# Safety_Logic.net
KiCad netlist of a schematic drawn in Altium Designer
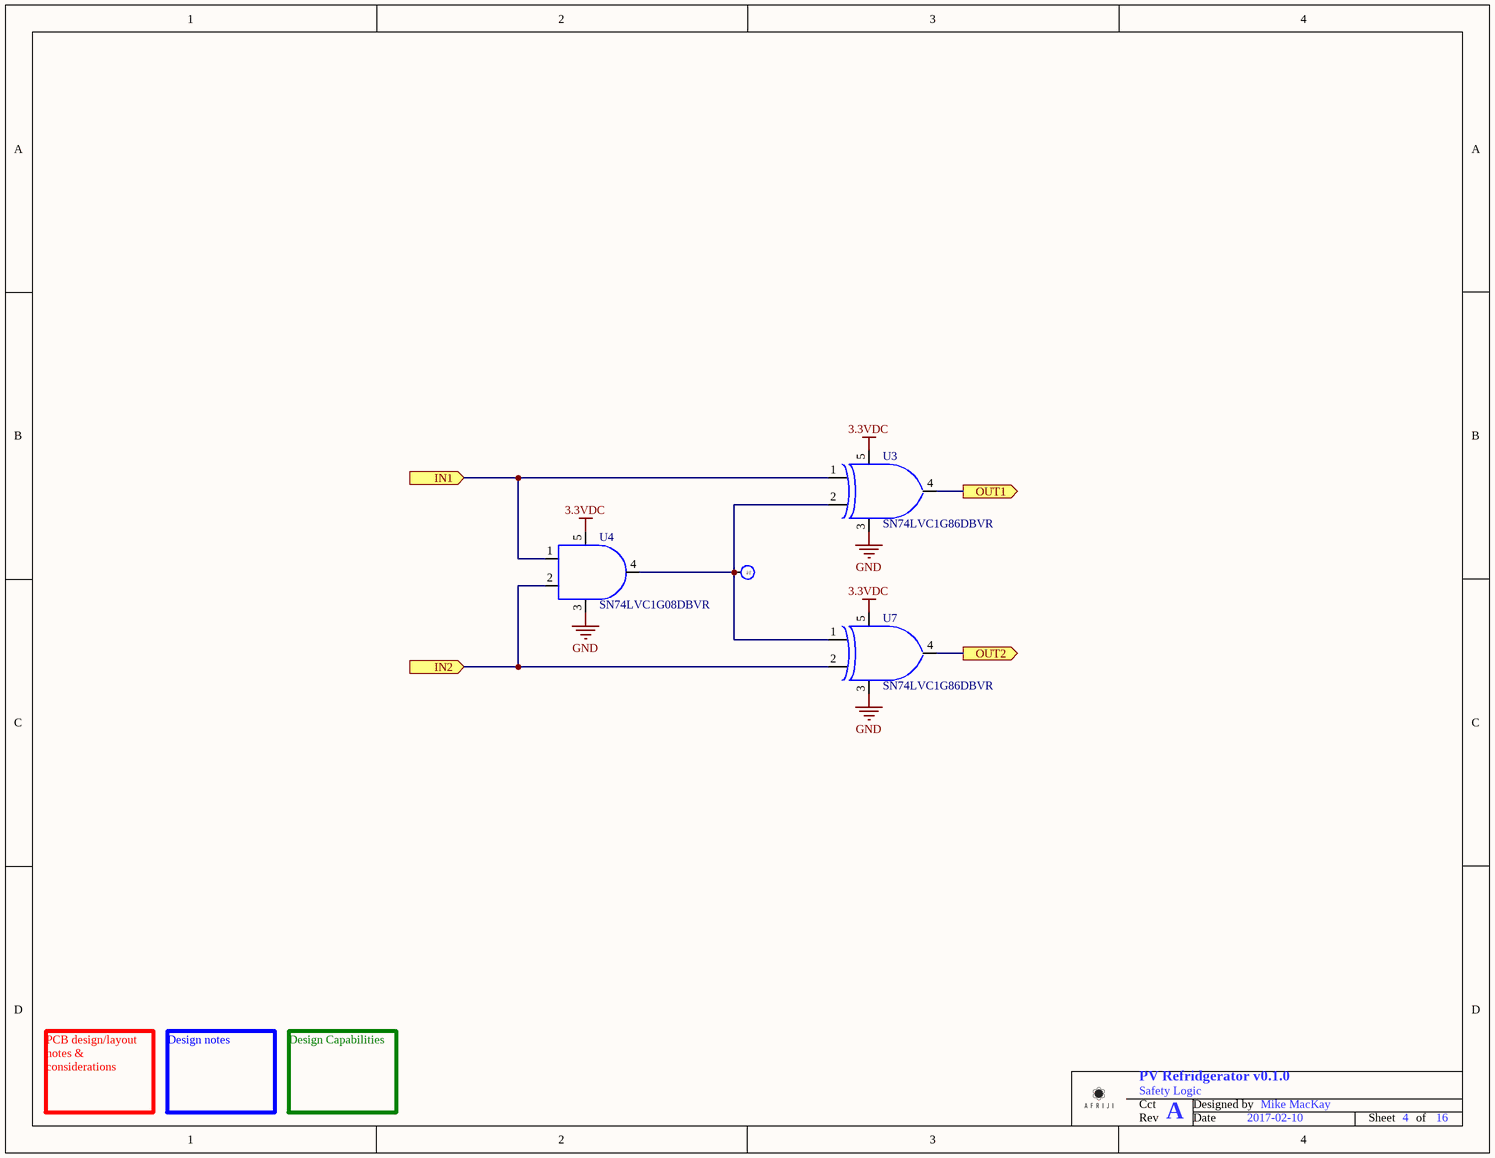
[diagram p0: Safety Logic.SchDoc]

(export (version "E")
  (design (tool "Eeschema 10.0.6"))
  (components
    (comp (ref "TP4")
      (value "Test Clip")
      (footprint "SMT Test Clip")
      (fields
        (field (name "MANUFACTURER") "TE Connectivity AMP Connectors")
        (field (name "MANUFACTURER PART NUMBER") "RCU-0C")
      )
      (libsource (lib "Integrated Component Library") (part "Test Clip"))
    )
    (comp (ref "U3")
      (value "Single XOR Logic Gate")
      (footprint "SOT23-5")
      (fields
        (field (name "MANUFACTURER") "Texas Instruments")
        (field (name "MANUFACTURER PART NUMBER") "SN74LVC1G86DBVR")
      )
      (libsource (lib "Local Library") (part "Single XOR Logic Gate"))
    )
    (comp (ref "U4")
      (value "Single AND Logic Gate")
      (footprint "SOT23-5")
      (fields
        (field (name "MANUFACTURER") "Texas Instruments")
        (field (name "MANUFACTURER PART NUMBER") "SN74LVC1G08DBVR")
      )
      (libsource (lib "Local Library") (part "Single AND Logic Gate"))
    )
    (comp (ref "U7")
      (value "Single XOR Logic Gate")
      (footprint "SOT23-5")
      (fields
        (field (name "MANUFACTURER") "Texas Instruments")
        (field (name "MANUFACTURER PART NUMBER") "SN74LVC1G86DBVR")
      )
      (libsource (lib "Local Library") (part "Single XOR Logic Gate"))
    )
  )
  (nets
    (net (code "1") (name "/IN1") (class "Default")
      (node (ref "U3") (pin "1") (pinfunction "A_1") (pintype "passive"))
      (node (ref "U4") (pin "1") (pinfunction "A_1") (pintype "passive"))
    )
    (net (code "2") (name "/IN2") (class "Default")
      (node (ref "U4") (pin "2") (pinfunction "B_2") (pintype "passive"))
      (node (ref "U7") (pin "2") (pinfunction "B_2") (pintype "passive"))
    )
    (net (code "3") (name "/OUT1") (class "Default")
      (node (ref "U3") (pin "4") (pinfunction "Y_4") (pintype "passive"))
    )
    (net (code "4") (name "/OUT2") (class "Default")
      (node (ref "U7") (pin "4") (pinfunction "Y_4") (pintype "passive"))
    )
    (net (code "5") (name "3.3VDC") (class "Default")
      (node (ref "U3") (pin "5") (pinfunction "Vcc_5") (pintype "passive"))
      (node (ref "U4") (pin "5") (pinfunction "Vcc_5") (pintype "passive"))
      (node (ref "U7") (pin "5") (pinfunction "Vcc_5") (pintype "passive"))
    )
    (net (code "6") (name "GND") (class "Default")
      (node (ref "U3") (pin "3") (pinfunction "Gnd_3") (pintype "passive"))
      (node (ref "U4") (pin "3") (pinfunction "Gnd_3") (pintype "passive"))
      (node (ref "U7") (pin "3") (pinfunction "Gnd_3") (pintype "passive"))
    )
    (net (code "7") (name "Net-(U3-B)") (class "Default")
      (node (ref "TP4") (pin "1") (pinfunction "1_1") (pintype "passive"))
      (node (ref "U3") (pin "2") (pinfunction "B_2") (pintype "passive"))
      (node (ref "U4") (pin "4") (pinfunction "Y_4") (pintype "passive"))
      (node (ref "U7") (pin "1") (pinfunction "A_1") (pintype "passive"))
    )
  )
)
